# Btn_Ctrl.net
KiCad netlist of a schematic drawn in Altium Designer
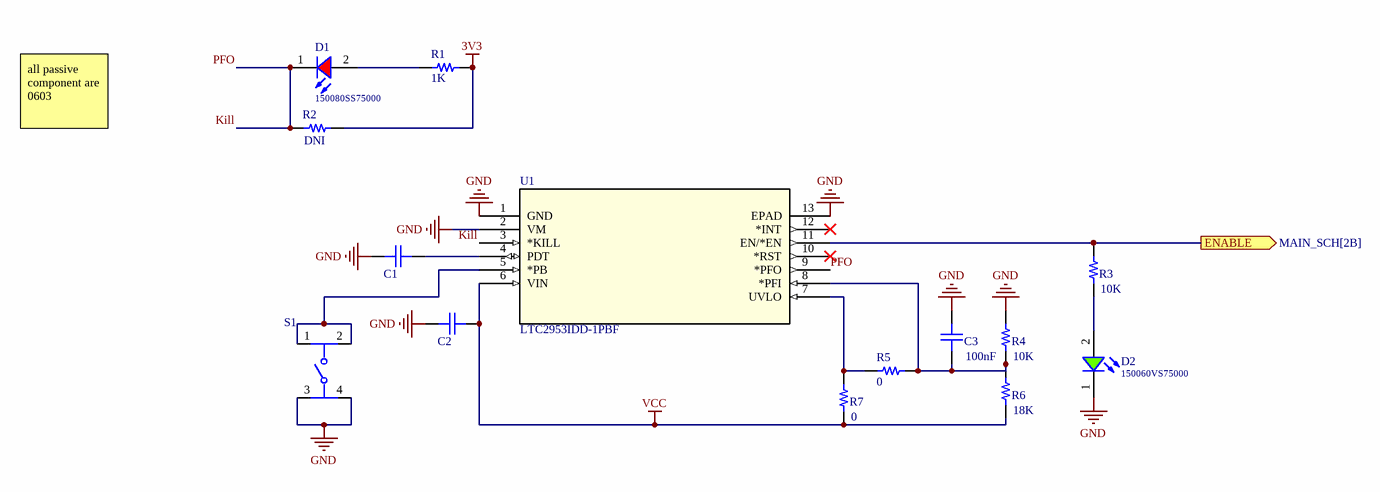
[diagram p0: Btn_Ctrl.SchDoc]

(export (version "E")
  (design (tool "Eeschema 10.0.6"))
  (components
    (comp (ref "C1")
      (value "Capacitor")
      (footprint "FP-CL10-IPC_B")
      (description "SMT Capacitor")
      (libsource (lib "ILH") (part "Capacitor"))
    )
    (comp (ref "C2")
      (value "Capacitor")
      (footprint "FP-CL10-IPC_B")
      (description "SMT Capacitor")
      (libsource (lib "ILH") (part "Capacitor"))
    )
    (comp (ref "C3")
      (value "100nF")
      (footprint "FP-CL10-IPC_B")
      (description "SMT Capacitor")
      (libsource (lib "ILH") (part "Capacitor"))
    )
    (comp (ref "D1")
      (value "150080SS75000")
      (footprint "WL-SMCW_0805")
      (description "WL-SMCW SMT Mono-color Chip LED Waterclear, size 0805, Super Red, 1.9V, 140deg")
      (fields (field (name "PUBLISHER") "Wurth Elektronik"))
      (libsource (lib "ILH") (part "LED RED"))
    )
    (comp (ref "D2")
      (value "150060VS75000")
      (footprint "WL-SMCW_0603_H=0.7mm")
      (description "WL-SMCW SMT Mono-color Chip LED Waterclear, size 0603, Bright Green, 2V, 140deg")
      (fields (field (name "PUBLISHER") "Wurth Elektronik"))
      (libsource (lib "ILH") (part "Symbol"))
    )
    (comp (ref "R1")
      (value "1K")
      (footprint "R_10k_JLC")
      (fields
        (field (name "JLCPCB PART #") "C25804")
        (field (name "TOLERANCE") "1%")
        (field (name "POWER") "100mW")
      )
      (libsource (lib "ILH") (part "Resistor"))
    )
    (comp (ref "R2")
      (value "DNI")
      (footprint "R_10k_JLC")
      (fields
        (field (name "JLCPCB PART #") "C25804")
        (field (name "TOLERANCE") "1%")
        (field (name "POWER") "100mW")
      )
      (libsource (lib "ILH") (part "Resistor"))
    )
    (comp (ref "R3")
      (value "10K")
      (footprint "R_10k_JLC")
      (fields
        (field (name "JLCPCB PART #") "C25804")
        (field (name "TOLERANCE") "1%")
        (field (name "POWER") "100mW")
      )
      (libsource (lib "ILH") (part "Resistor"))
    )
    (comp (ref "R4")
      (value "10K")
      (footprint "R_10k_JLC")
      (fields
        (field (name "JLCPCB PART #") "C25804")
        (field (name "TOLERANCE") "1%")
        (field (name "POWER") "100mW")
      )
      (libsource (lib "ILH") (part "Resistor"))
    )
    (comp (ref "R5")
      (value "0")
      (footprint "R_10k_JLC")
      (fields
        (field (name "JLCPCB PART #") "C25804")
        (field (name "TOLERANCE") "1%")
        (field (name "POWER") "100mW")
      )
      (libsource (lib "ILH") (part "Resistor"))
    )
    (comp (ref "R6")
      (value "18K")
      (footprint "R_10k_JLC")
      (fields
        (field (name "JLCPCB PART #") "C25804")
        (field (name "TOLERANCE") "1%")
        (field (name "POWER") "100mW")
      )
      (libsource (lib "ILH") (part "Resistor"))
    )
    (comp (ref "R7")
      (value "0")
      (footprint "R_10k_JLC")
      (fields
        (field (name "JLCPCB PART #") "C25804")
        (field (name "TOLERANCE") "1%")
        (field (name "POWER") "100mW")
      )
      (libsource (lib "ILH") (part "Resistor"))
    )
    (comp (ref "S1")
      (value "PTS645SH50SMTR92LFS")
      (footprint "FP-PTS645SM43SMTR92LFS-MFG")
      (description "Switch Tactile N.O. SPST Round Button Gull Wing 0.05A 12VDC 100000Cycles 1.96N SMD T/R")
      (libsource (lib "ILH") (part "1adf0dd01260c80cf25a44bfd6b99ba"))
    )
    (comp (ref "U1")
      (value "LTC2953IDD-1PBF")
      (footprint "DFN-12_DD_LIT")
      (description "No Description Available")
      (libsource (lib "LTC2953IDD-1PBF") (part "LTC2953IDD-1PBF"))
    )
  )
  (nets
    (net (code "1") (name "/ENABLE") (class "Default")
      (node (ref "R3") (pin "2") (pinfunction "2_2") (pintype "passive"))
      (node (ref "U1") (pin "11") (pinfunction "EN/*EN_11") (pintype "output"))
    )
    (net (code "2") (name "/Kill") (class "Default")
      (node (ref "D1") (pin "1") (pinfunction "K_1") (pintype "passive"))
      (node (ref "R2") (pin "1") (pinfunction "1_1") (pintype "passive"))
      (node (ref "U1") (pin "3") (pinfunction "*KILL_3") (pintype "input"))
      (node (ref "U1") (pin "9") (pinfunction "*PFO_9") (pintype "output"))
    )
    (net (code "3") (name "3V3") (class "Default")
      (node (ref "R1") (pin "2") (pinfunction "2_2") (pintype "passive"))
      (node (ref "R2") (pin "2") (pinfunction "2_2") (pintype "passive"))
    )
    (net (code "4") (name "GND") (class "Default")
      (node (ref "C1") (pin "1") (pinfunction "1_1") (pintype "passive"))
      (node (ref "C2") (pin "2") (pinfunction "2_2") (pintype "passive"))
      (node (ref "C3") (pin "2") (pinfunction "2_2") (pintype "passive"))
      (node (ref "D2") (pin "1") (pinfunction "K_1") (pintype "passive"))
      (node (ref "R4") (pin "2") (pinfunction "2_2") (pintype "passive"))
      (node (ref "S1") (pin "3") (pinfunction "3_3") (pintype "passive"))
      (node (ref "S1") (pin "4") (pinfunction "4_4") (pintype "passive"))
      (node (ref "U1") (pin "1") (pinfunction "GND_1") (pintype "power_in"))
      (node (ref "U1") (pin "13") (pinfunction "EPAD_13") (pintype "passive"))
      (node (ref "U1") (pin "2") (pinfunction "VM_2") (pintype "power_in"))
    )
    (net (code "5") (name "Net-(D1-A)") (class "Default")
      (node (ref "D1") (pin "2") (pinfunction "A_2") (pintype "passive"))
      (node (ref "R1") (pin "1") (pinfunction "1_1") (pintype "passive"))
    )
    (net (code "6") (name "Net-(D2-A)") (class "Default")
      (node (ref "D2") (pin "2") (pinfunction "A_2") (pintype "passive"))
      (node (ref "R3") (pin "1") (pinfunction "1_1") (pintype "passive"))
    )
    (net (code "7") (name "Net-(U1-*PB)") (class "Default")
      (node (ref "S1") (pin "1") (pinfunction "1_1") (pintype "passive"))
      (node (ref "S1") (pin "2") (pinfunction "2_2") (pintype "passive"))
      (node (ref "U1") (pin "5") (pinfunction "*PB_5") (pintype "input"))
    )
    (net (code "8") (name "Net-(U1-*PFI)") (class "Default")
      (node (ref "C3") (pin "1") (pinfunction "1_1") (pintype "passive"))
      (node (ref "R4") (pin "1") (pinfunction "1_1") (pintype "passive"))
      (node (ref "R5") (pin "1") (pinfunction "1_1") (pintype "passive"))
      (node (ref "R6") (pin "2") (pinfunction "2_2") (pintype "passive"))
      (node (ref "U1") (pin "8") (pinfunction "*PFI_8") (pintype "input"))
    )
    (net (code "9") (name "Net-(U1-PDT)") (class "Default")
      (node (ref "C1") (pin "2") (pinfunction "2_2") (pintype "passive"))
      (node (ref "U1") (pin "4") (pinfunction "PDT_4") (pintype "bidirectional"))
    )
    (net (code "10") (name "Net-(U1-UVLO)") (class "Default")
      (node (ref "R5") (pin "2") (pinfunction "2_2") (pintype "passive"))
      (node (ref "R7") (pin "2") (pinfunction "2_2") (pintype "passive"))
      (node (ref "U1") (pin "7") (pinfunction "UVLO_7") (pintype "input"))
    )
    (net (code "11") (name "VCC") (class "Default")
      (node (ref "C2") (pin "1") (pinfunction "1_1") (pintype "passive"))
      (node (ref "R6") (pin "1") (pinfunction "1_1") (pintype "passive"))
      (node (ref "R7") (pin "1") (pinfunction "1_1") (pintype "passive"))
      (node (ref "U1") (pin "6") (pinfunction "VIN_6") (pintype "input"))
    )
    (net (code "12") (name "unconnected-(U1-*INT-Pad12)") (class "Default")
      (node (ref "U1") (pin "12") (pinfunction "*INT_12") (pintype "output+no_connect"))
    )
    (net (code "13") (name "unconnected-(U1-*RST-Pad10)") (class "Default")
      (node (ref "U1") (pin "10") (pinfunction "*RST_10") (pintype "output+no_connect"))
    )
  )
)
